# FT-991A_PAT.net
KiCad netlist of a schematic drawn in EAGLE
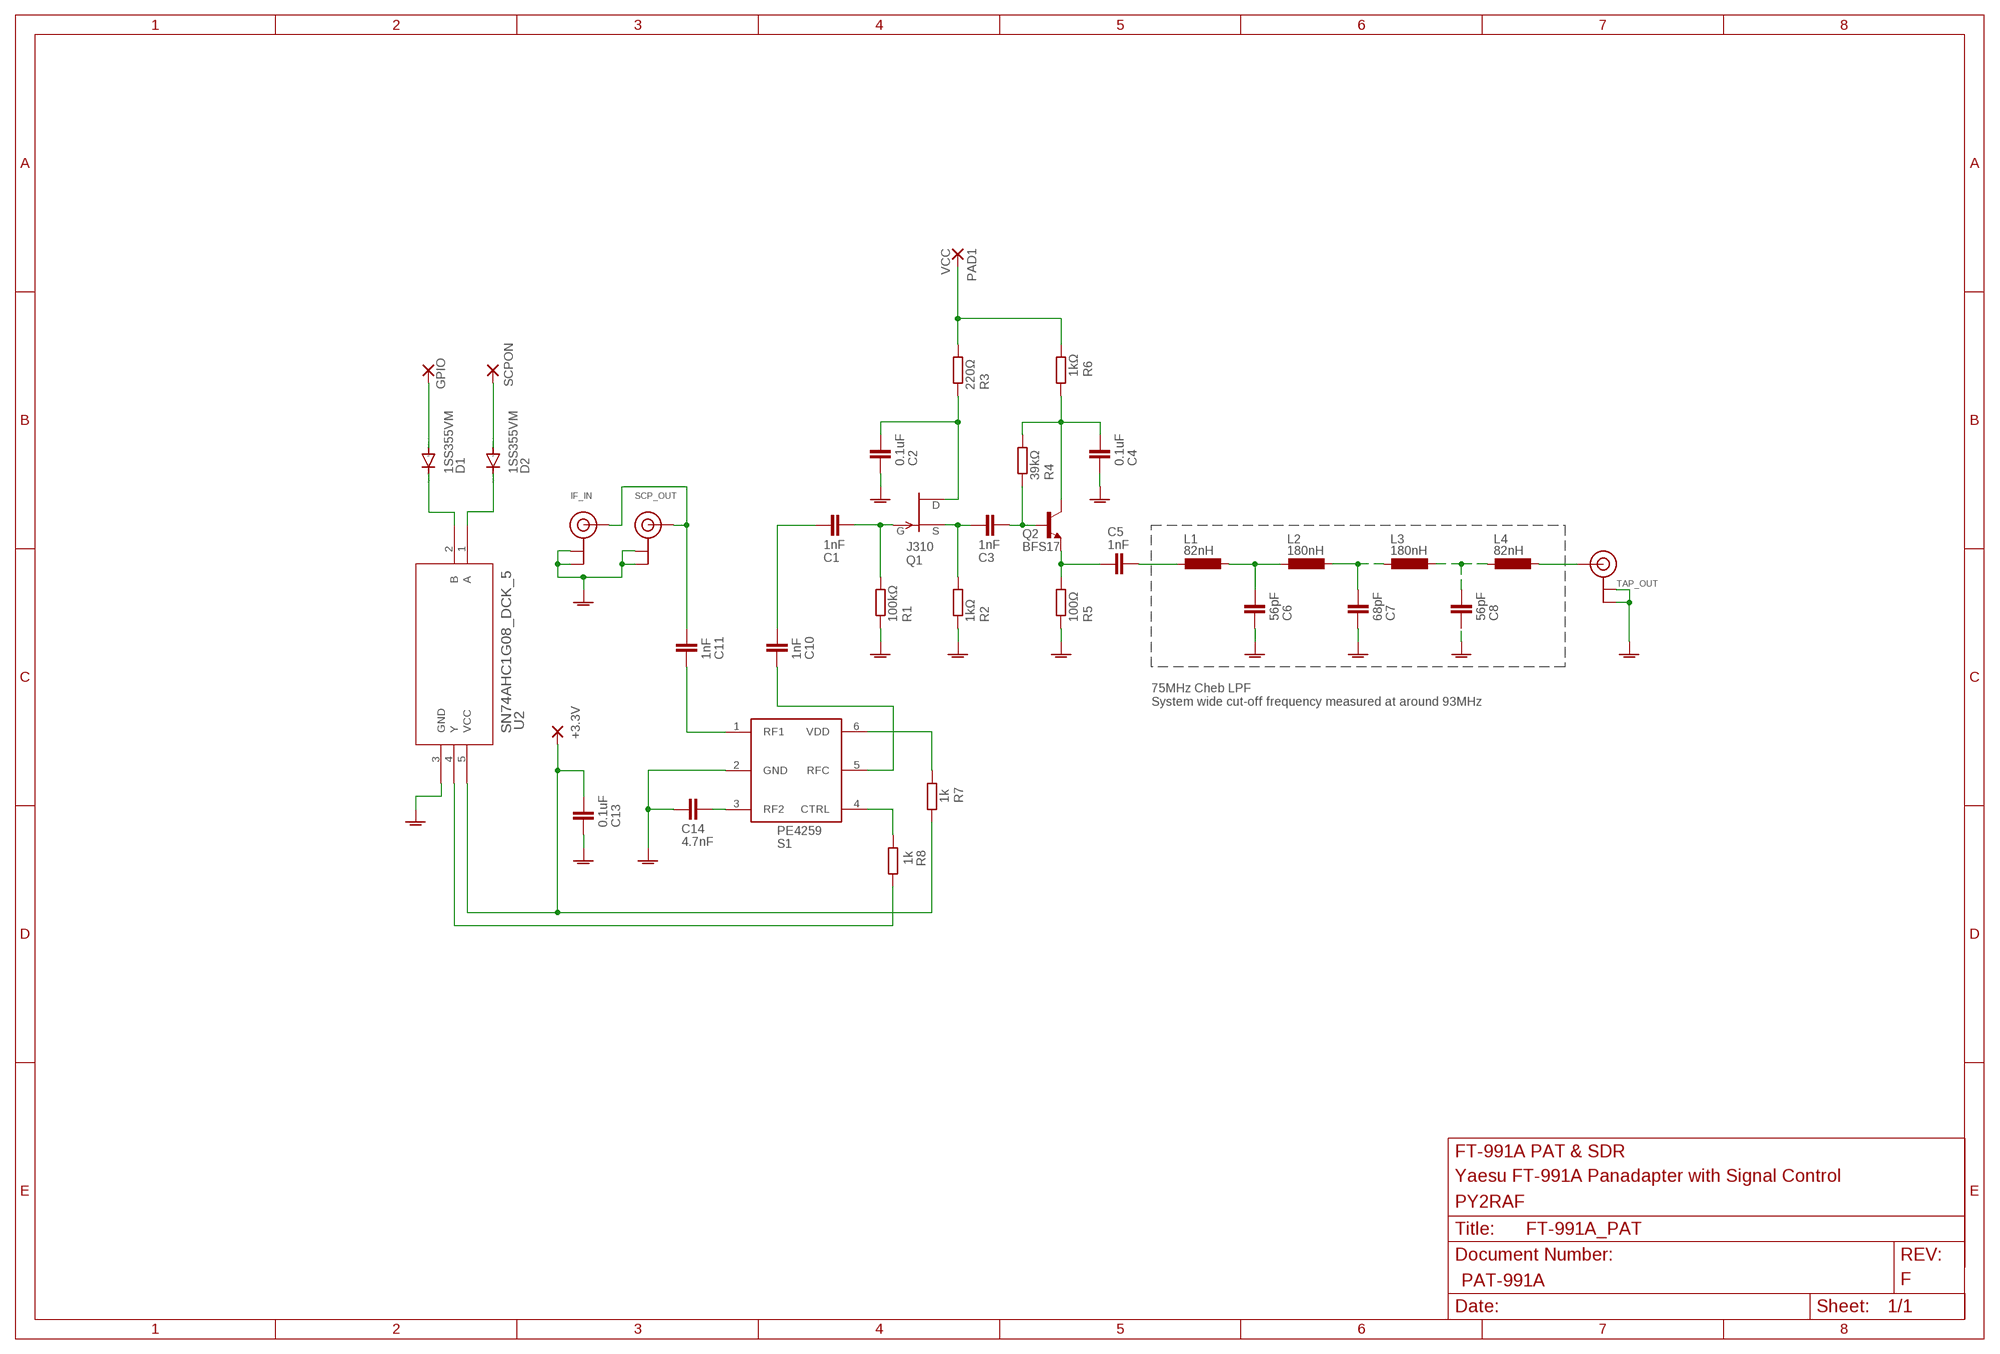
[diagram p0: schematic, sheet 1]

(export (version "E")
  (design (tool "Eeschema 10.0.6"))
  (components
    (comp (ref "+3.3V")
      (value "WIREPADSMD1,27-254")
      (footprint "eagle-import:SMD1,27-2,54")
      (libsource (lib "eagle-import") (part "wirepad_412_WIREPADSMD1,27-254"))
    )
    (comp (ref "C1")
      (value "1nF")
      (footprint "eagle-import:C0805K")
      (libsource (lib "eagle-import") (part "C-EUC0805K"))
    )
    (comp (ref "C2")
      (value "0.1uF")
      (footprint "eagle-import:C0805K")
      (libsource (lib "eagle-import") (part "C-EUC0805K"))
    )
    (comp (ref "C3")
      (value "1nF")
      (footprint "eagle-import:C0805K")
      (libsource (lib "eagle-import") (part "C-EUC0805K"))
    )
    (comp (ref "C4")
      (value "0.1uF")
      (footprint "eagle-import:C0805K")
      (libsource (lib "eagle-import") (part "C-EUC0805K"))
    )
    (comp (ref "C5")
      (value "1nF")
      (footprint "eagle-import:C0805K")
      (libsource (lib "eagle-import") (part "C-EUC0805K"))
    )
    (comp (ref "C6")
      (value "56pF")
      (footprint "eagle-import:C0805K")
      (libsource (lib "eagle-import") (part "C-EUC0805K"))
    )
    (comp (ref "C7")
      (value "68pF")
      (footprint "eagle-import:C0805K")
      (libsource (lib "eagle-import") (part "C-EUC0805K"))
    )
    (comp (ref "C8")
      (value "56pF")
      (footprint "eagle-import:C0805K")
      (libsource (lib "eagle-import") (part "C-EUC0805K"))
    )
    (comp (ref "C10")
      (value "1nF")
      (footprint "eagle-import:C0805K")
      (libsource (lib "eagle-import") (part "C-EUC0805K"))
    )
    (comp (ref "C11")
      (value "1nF")
      (footprint "eagle-import:C0805K")
      (libsource (lib "eagle-import") (part "C-EUC0805K"))
    )
    (comp (ref "C13")
      (value "0.1uF")
      (footprint "eagle-import:C0805K")
      (libsource (lib "eagle-import") (part "C-EUC0805K"))
    )
    (comp (ref "C14")
      (value "4.7nF")
      (footprint "eagle-import:C0805K")
      (libsource (lib "eagle-import") (part "C-EUC0805K"))
    )
    (comp (ref "D1")
      (value "1SS355VM")
      (footprint "eagle-import:SOD323-W")
      (libsource (lib "eagle-import") (part "DIODE-SOD323-W"))
    )
    (comp (ref "D2")
      (value "1SS355VM")
      (footprint "eagle-import:SOD323-W")
      (libsource (lib "eagle-import") (part "DIODE-SOD323-W"))
    )
    (comp (ref "GPIO")
      (value "GPIO")
      (footprint "eagle-import:SMD1,27-2,54")
      (libsource (lib "eagle-import") (part "wirepad_412_WIREPADSMD1,27-254"))
    )
    (comp (ref "L1")
      (value "82nH")
      (footprint "eagle-import:L0805")
      (libsource (lib "eagle-import") (part "L-EU"))
    )
    (comp (ref "L2")
      (value "180nH")
      (footprint "eagle-import:L0805")
      (libsource (lib "eagle-import") (part "L-EU"))
    )
    (comp (ref "L3")
      (value "180nH")
      (footprint "eagle-import:L0805")
      (libsource (lib "eagle-import") (part "L-EU"))
    )
    (comp (ref "L4")
      (value "82nH")
      (footprint "eagle-import:L0805")
      (libsource (lib "eagle-import") (part "L-EU"))
    )
    (comp (ref "PAD1")
      (value "VCC")
      (footprint "eagle-import:SMD2,54-5,08")
      (libsource (lib "eagle-import") (part "WIREPADSMD2,54-5,08"))
    )
    (comp (ref "Q1")
      (value "J310")
      (footprint "eagle-import:SOT23")
      (fields (field (name "SPICEPREFIX") "J"))
      (libsource (lib "eagle-import") (part "?20SST1"))
    )
    (comp (ref "Q2")
      (value "BFS17")
      (footprint "eagle-import:SOT23")
      (libsource (lib "eagle-import") (part "BC846"))
    )
    (comp (ref "R1")
      (value "100kΩ")
      (footprint "eagle-import:R0805")
      (libsource (lib "eagle-import") (part "R-EU_R0805"))
    )
    (comp (ref "R2")
      (value "1kΩ")
      (footprint "eagle-import:R0805")
      (libsource (lib "eagle-import") (part "R-EU_R0805"))
    )
    (comp (ref "R3")
      (value "220Ω")
      (footprint "eagle-import:R0805")
      (libsource (lib "eagle-import") (part "R-EU_R0805"))
    )
    (comp (ref "R4")
      (value "39kΩ")
      (footprint "eagle-import:R0805")
      (libsource (lib "eagle-import") (part "R-EU_R0805"))
    )
    (comp (ref "R5")
      (value "100Ω")
      (footprint "eagle-import:R0805")
      (libsource (lib "eagle-import") (part "R-EU_R0805"))
    )
    (comp (ref "R6")
      (value "1kΩ")
      (footprint "eagle-import:R1206")
      (libsource (lib "eagle-import") (part "R-EU_R1206"))
    )
    (comp (ref "R7")
      (value "1k")
      (footprint "eagle-import:R0805")
      (libsource (lib "eagle-import") (part "R-EU_R0805"))
    )
    (comp (ref "R8")
      (value "1k")
      (footprint "eagle-import:R0805")
      (libsource (lib "eagle-import") (part "R-EU_R0805"))
    )
    (comp (ref "S1")
      (value "PE4259")
      (footprint "eagle-import:SC-70")
      (libsource (lib "eagle-import") (part "PE4259"))
    )
    (comp (ref "SCPON")
      (value "SCPON")
      (footprint "eagle-import:SMD1,27-2,54")
      (libsource (lib "eagle-import") (part "wirepad_412_WIREPADSMD1,27-254"))
    )
    (comp (ref "TAP_OUT")
      (value "TAP_OUT")
      (footprint "eagle-import:U.FL")
      (libsource (lib "eagle-import") (part "ANTENNA_U.FL"))
    )
    (comp (ref "U2")
      (value "SN74AHC1G08_DCK_5")
      (footprint "eagle-import:DCK5")
      (fields
        (field (name "GENERIC_PART_NUMBER") "SN74AHC1G08")
        (field (name "MANUFACTURER") "Texas Instruments")
        (field (name "MANUFACTURER_PART_NUMBER") "sn74ahc1g08_dck_5")
      )
      (libsource (lib "eagle-import") (part "SN74AHC1G08_DCK_5"))
    )
    (comp (ref "X1")
      (value "SCP_OUT")
      (footprint "eagle-import:U.FL")
      (libsource (lib "eagle-import") (part "ANTENNA_U.FL"))
    )
    (comp (ref "X2")
      (value "IF_IN")
      (footprint "eagle-import:U.FL")
      (libsource (lib "eagle-import") (part "ANTENNA_U.FL"))
    )
  )
  (nets
    (net (code "1") (name "GNDA") (class "Default")
      (node (ref "C13") (pin "2") (pinfunction "2_2") (pintype "passive"))
      (node (ref "C14") (pin "1") (pinfunction "1_1") (pintype "passive"))
      (node (ref "C2") (pin "2") (pinfunction "2_2") (pintype "passive"))
      (node (ref "C4") (pin "2") (pinfunction "2_2") (pintype "passive"))
      (node (ref "C6") (pin "2") (pinfunction "2_2") (pintype "passive"))
      (node (ref "C7") (pin "2") (pinfunction "2_2") (pintype "passive"))
      (node (ref "C8") (pin "2") (pinfunction "2_2") (pintype "passive"))
      (node (ref "R1") (pin "1") (pinfunction "1_1") (pintype "passive"))
      (node (ref "R2") (pin "1") (pinfunction "1_1") (pintype "passive"))
      (node (ref "R5") (pin "2") (pinfunction "2_2") (pintype "passive"))
      (node (ref "S1") (pin "2") (pinfunction "GND_2") (pintype "bidirectional"))
      (node (ref "TAP_OUT") (pin "1") (pinfunction "GND_1") (pintype "passive"))
      (node (ref "TAP_OUT") (pin "2") (pinfunction "GND_2") (pintype "passive"))
      (node (ref "U2") (pin "3") (pinfunction "GND_3") (pintype "power_in"))
      (node (ref "X1") (pin "1") (pinfunction "GND_1") (pintype "passive"))
      (node (ref "X1") (pin "2") (pinfunction "GND_2") (pintype "passive"))
      (node (ref "X2") (pin "1") (pinfunction "GND_1") (pintype "passive"))
      (node (ref "X2") (pin "2") (pinfunction "GND_2") (pintype "passive"))
    )
    (net (code "2") (name "Net-(+3.3V-P)") (class "Default")
      (node (ref "+3.3V") (pin "1") (pinfunction "P_1") (pintype "passive"))
      (node (ref "C13") (pin "1") (pinfunction "1_1") (pintype "passive"))
      (node (ref "R7") (pin "1") (pinfunction "1_1") (pintype "passive"))
      (node (ref "U2") (pin "5") (pinfunction "VCC_5") (pintype "power_in"))
    )
    (net (code "3") (name "Net-(C1-Pad1)") (class "Default")
      (node (ref "C1") (pin "1") (pinfunction "1_1") (pintype "passive"))
      (node (ref "C10") (pin "1") (pinfunction "1_1") (pintype "passive"))
    )
    (net (code "4") (name "Net-(C5-Pad2)") (class "Default")
      (node (ref "C5") (pin "2") (pinfunction "2_2") (pintype "passive"))
      (node (ref "L1") (pin "1") (pinfunction "1_1") (pintype "passive"))
    )
    (net (code "5") (name "Net-(C6-Pad1)") (class "Default")
      (node (ref "C6") (pin "1") (pinfunction "1_1") (pintype "passive"))
      (node (ref "L1") (pin "2") (pinfunction "2_2") (pintype "passive"))
      (node (ref "L2") (pin "1") (pinfunction "1_1") (pintype "passive"))
    )
    (net (code "6") (name "Net-(C7-Pad1)") (class "Default")
      (node (ref "C7") (pin "1") (pinfunction "1_1") (pintype "passive"))
      (node (ref "L2") (pin "2") (pinfunction "2_2") (pintype "passive"))
      (node (ref "L3") (pin "1") (pinfunction "1_1") (pintype "passive"))
    )
    (net (code "7") (name "Net-(C8-Pad1)") (class "Default")
      (node (ref "C8") (pin "1") (pinfunction "1_1") (pintype "passive"))
      (node (ref "L3") (pin "2") (pinfunction "2_2") (pintype "passive"))
      (node (ref "L4") (pin "1") (pinfunction "1_1") (pintype "passive"))
    )
    (net (code "8") (name "Net-(GPIO-P)") (class "Default")
      (node (ref "D1") (pin "A") (pinfunction "A_A") (pintype "passive"))
      (node (ref "GPIO") (pin "1") (pinfunction "P_1") (pintype "passive"))
    )
    (net (code "9") (name "Net-(PAD1-P)") (class "Default")
      (node (ref "PAD1") (pin "1") (pinfunction "P_1") (pintype "passive"))
      (node (ref "R3") (pin "2") (pinfunction "2_2") (pintype "passive"))
      (node (ref "R6") (pin "1") (pinfunction "1_1") (pintype "passive"))
    )
    (net (code "10") (name "Net-(Q1-D)") (class "Default")
      (node (ref "C2") (pin "1") (pinfunction "1_1") (pintype "passive"))
      (node (ref "Q1") (pin "1") (pinfunction "D_1") (pintype "passive"))
      (node (ref "R3") (pin "1") (pinfunction "1_1") (pintype "passive"))
    )
    (net (code "11") (name "Net-(Q1-G)") (class "Default")
      (node (ref "C1") (pin "2") (pinfunction "2_2") (pintype "passive"))
      (node (ref "Q1") (pin "3") (pinfunction "G_3") (pintype "passive"))
      (node (ref "R1") (pin "2") (pinfunction "2_2") (pintype "passive"))
    )
    (net (code "12") (name "Net-(Q1-S)") (class "Default")
      (node (ref "C3") (pin "1") (pinfunction "1_1") (pintype "passive"))
      (node (ref "Q1") (pin "2") (pinfunction "S_2") (pintype "passive"))
      (node (ref "R2") (pin "2") (pinfunction "2_2") (pintype "passive"))
    )
    (net (code "13") (name "Net-(Q2-B)") (class "Default")
      (node (ref "C3") (pin "2") (pinfunction "2_2") (pintype "passive"))
      (node (ref "Q2") (pin "1") (pinfunction "B_1") (pintype "passive"))
      (node (ref "R4") (pin "2") (pinfunction "2_2") (pintype "passive"))
    )
    (net (code "14") (name "Net-(Q2-C)") (class "Default")
      (node (ref "C4") (pin "1") (pinfunction "1_1") (pintype "passive"))
      (node (ref "Q2") (pin "3") (pinfunction "C_3") (pintype "passive"))
      (node (ref "R4") (pin "1") (pinfunction "1_1") (pintype "passive"))
      (node (ref "R6") (pin "2") (pinfunction "2_2") (pintype "passive"))
    )
    (net (code "15") (name "Net-(Q2-E)") (class "Default")
      (node (ref "C5") (pin "1") (pinfunction "1_1") (pintype "passive"))
      (node (ref "Q2") (pin "2") (pinfunction "E_2") (pintype "passive"))
      (node (ref "R5") (pin "1") (pinfunction "1_1") (pintype "passive"))
    )
    (net (code "16") (name "Net-(S1-CTRL)") (class "Default")
      (node (ref "R8") (pin "2") (pinfunction "2_2") (pintype "passive"))
      (node (ref "S1") (pin "4") (pinfunction "CTRL_4") (pintype "input"))
    )
    (net (code "17") (name "Net-(S1-RF1)") (class "Default")
      (node (ref "C11") (pin "2") (pinfunction "2_2") (pintype "passive"))
      (node (ref "S1") (pin "1") (pinfunction "RF1_1") (pintype "bidirectional"))
    )
    (net (code "18") (name "Net-(S1-RF2)") (class "Default")
      (node (ref "C14") (pin "2") (pinfunction "2_2") (pintype "passive"))
      (node (ref "S1") (pin "3") (pinfunction "RF2_3") (pintype "bidirectional"))
    )
    (net (code "19") (name "Net-(S1-RFC)") (class "Default")
      (node (ref "C10") (pin "2") (pinfunction "2_2") (pintype "passive"))
      (node (ref "S1") (pin "5") (pinfunction "RFC_5") (pintype "bidirectional"))
    )
    (net (code "20") (name "Net-(S1-VDD)") (class "Default")
      (node (ref "R7") (pin "2") (pinfunction "2_2") (pintype "passive"))
      (node (ref "S1") (pin "6") (pinfunction "VDD_6") (pintype "power_in"))
    )
    (net (code "21") (name "Net-(SCPON-P)") (class "Default")
      (node (ref "D2") (pin "A") (pinfunction "A_A") (pintype "passive"))
      (node (ref "SCPON") (pin "1") (pinfunction "P_1") (pintype "passive"))
    )
    (net (code "22") (name "Net-(TAP_OUT-SIGNAL)") (class "Default")
      (node (ref "L4") (pin "2") (pinfunction "2_2") (pintype "passive"))
      (node (ref "TAP_OUT") (pin "3") (pinfunction "SIGNAL_3") (pintype "passive"))
    )
    (net (code "23") (name "Net-(U2-A)") (class "Default")
      (node (ref "D2") (pin "C") (pinfunction "C_C") (pintype "passive"))
      (node (ref "U2") (pin "1") (pinfunction "A_1") (pintype "input"))
    )
    (net (code "24") (name "Net-(U2-B)") (class "Default")
      (node (ref "D1") (pin "C") (pinfunction "C_C") (pintype "passive"))
      (node (ref "U2") (pin "2") (pinfunction "B_2") (pintype "input"))
    )
    (net (code "25") (name "Net-(U2-Y)") (class "Default")
      (node (ref "R8") (pin "1") (pinfunction "1_1") (pintype "passive"))
      (node (ref "U2") (pin "4") (pinfunction "Y_4") (pintype "output"))
    )
    (net (code "26") (name "Net-(X1-SIGNAL)") (class "Default")
      (node (ref "C11") (pin "1") (pinfunction "1_1") (pintype "passive"))
      (node (ref "X1") (pin "3") (pinfunction "SIGNAL_3") (pintype "passive"))
      (node (ref "X2") (pin "3") (pinfunction "SIGNAL_3") (pintype "passive"))
    )
  )
)
